# 2_0.net
KiCad netlist of a schematic drawn in Altium Designer
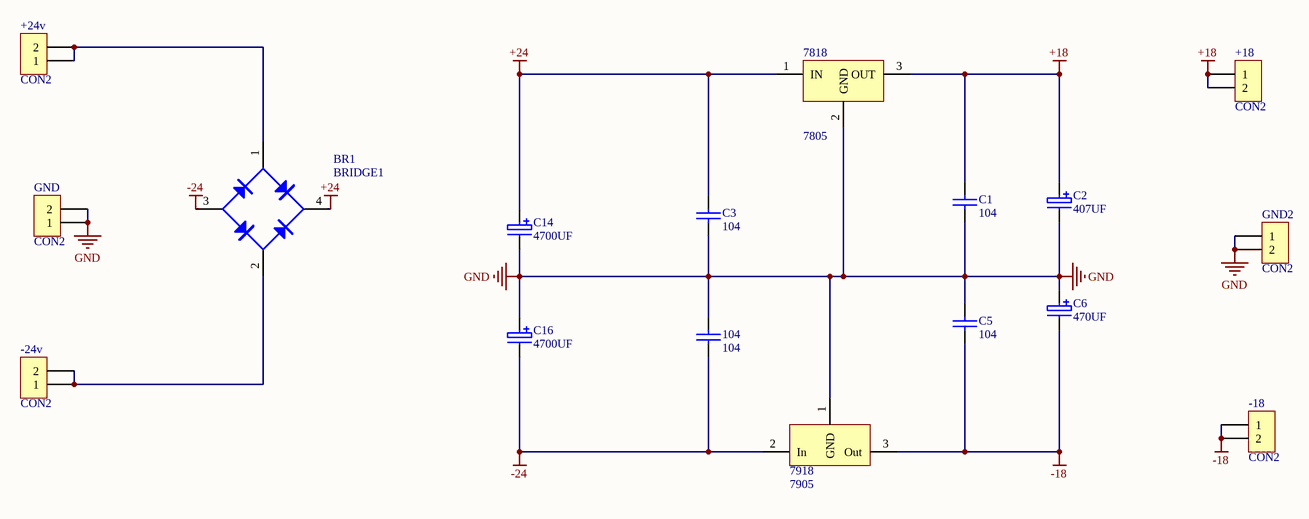
[diagram p0: 电源2.0.SchDoc]

(export (version "E")
  (design (tool "Eeschema 10.0.6"))
  (components
    (comp (ref "+18")
      (value "CON2")
      (footprint "2P-200")
      (description "Connector")
      (libsource (lib "接口") (part "CON2"))
    )
    (comp (ref "+24v")
      (value "CON2")
      (footprint "2P-200")
      (description "Connector")
      (libsource (lib "") (part "CON2_1"))
    )
    (comp (ref "-18")
      (value "CON2")
      (footprint "2P-200")
      (description "Connector")
      (libsource (lib "接口") (part "CON2"))
    )
    (comp (ref "-24v")
      (value "CON2")
      (footprint "2P-200")
      (description "Connector")
      (libsource (lib "") (part "CON2_1"))
    )
    (comp (ref "104") (value "104") (footprint "CAP2") (libsource (lib "C电容") (part "CAP1")))
    (comp (ref "7818") (value "7805") (footprint "TO-220") (libsource (lib "稳压管") (part "7805")))
    (comp (ref "7918") (value "7905") (footprint "TO-220") (libsource (lib "稳压管") (part "7905")))
    (comp (ref "BR1")
      (value "BRIDGE1")
      (footprint "D3")
      (description "BR")
      (libsource (lib "D硅堆") (part "BRIDGE1"))
    )
    (comp (ref "C1") (value "104") (footprint "CAP2") (libsource (lib "C电容") (part "CAP1")))
    (comp (ref "C2") (value "407UF") (footprint "CAO5") (libsource (lib "C电容") (part "CAP3")))
    (comp (ref "C3") (value "104") (footprint "CAP2") (libsource (lib "C电容") (part "CAP1")))
    (comp (ref "C5") (value "104") (footprint "CAP2") (libsource (lib "C电容") (part "CAP1")))
    (comp (ref "C6") (value "470UF") (footprint "CAO5") (libsource (lib "C电容") (part "CAP3")))
    (comp (ref "C14") (value "4700UF") (footprint "C22") (libsource (lib "C电容") (part "CAP3")))
    (comp (ref "C16") (value "4700UF") (footprint "C22") (libsource (lib "C电容") (part "CAP3")))
    (comp (ref "GND")
      (value "CON2")
      (footprint "2P-200")
      (description "Connector")
      (libsource (lib "") (part "CON2_1"))
    )
    (comp (ref "GND2")
      (value "CON2")
      (footprint "2P-200")
      (description "Connector")
      (libsource (lib "接口") (part "CON2"))
    )
  )
  (nets
    (net (code "1") (name "+18") (class "Default")
      (node (ref "+18") (pin "1") (pinfunction "1_1") (pintype "passive"))
      (node (ref "+18") (pin "2") (pinfunction "2_2") (pintype "passive"))
      (node (ref "7818") (pin "3") (pinfunction "OUT_3") (pintype "passive"))
      (node (ref "C1") (pin "1") (pinfunction "1_1") (pintype "passive"))
      (node (ref "C2") (pin "1") (pintype "passive"))
    )
    (net (code "2") (name "+24") (class "Default")
      (node (ref "7818") (pin "1") (pinfunction "IN_1") (pintype "passive"))
      (node (ref "BR1") (pin "4") (pinfunction "V+_4") (pintype "passive"))
      (node (ref "C14") (pin "1") (pintype "passive"))
      (node (ref "C3") (pin "1") (pinfunction "1_1") (pintype "passive"))
    )
    (net (code "3") (name "-18") (class "Default")
      (node (ref "-18") (pin "1") (pinfunction "1_1") (pintype "passive"))
      (node (ref "-18") (pin "2") (pinfunction "2_2") (pintype "passive"))
      (node (ref "7918") (pin "3") (pinfunction "Out_3") (pintype "passive"))
      (node (ref "C5") (pin "2") (pinfunction "2_2") (pintype "passive"))
      (node (ref "C6") (pin "2") (pintype "passive"))
    )
    (net (code "4") (name "-24") (class "Default")
      (node (ref "104") (pin "2") (pinfunction "2_2") (pintype "passive"))
      (node (ref "7918") (pin "2") (pinfunction "In_2") (pintype "passive"))
      (node (ref "BR1") (pin "3") (pinfunction "V-_3") (pintype "passive"))
      (node (ref "C16") (pin "2") (pintype "passive"))
    )
    (net (code "5") (name "GND") (class "Default")
      (node (ref "104") (pin "1") (pinfunction "1_1") (pintype "passive"))
      (node (ref "7818") (pin "2") (pinfunction "GND_2") (pintype "passive"))
      (node (ref "7918") (pin "1") (pinfunction "GND_1") (pintype "passive"))
      (node (ref "C1") (pin "2") (pinfunction "2_2") (pintype "passive"))
      (node (ref "C14") (pin "2") (pintype "passive"))
      (node (ref "C16") (pin "1") (pintype "passive"))
      (node (ref "C2") (pin "2") (pintype "passive"))
      (node (ref "C3") (pin "2") (pinfunction "2_2") (pintype "passive"))
      (node (ref "C5") (pin "1") (pinfunction "1_1") (pintype "passive"))
      (node (ref "C6") (pin "1") (pintype "passive"))
      (node (ref "GND") (pin "1") (pinfunction "1_1") (pintype "passive"))
      (node (ref "GND") (pin "2") (pinfunction "2_2") (pintype "passive"))
      (node (ref "GND2") (pin "1") (pinfunction "1_1") (pintype "passive"))
      (node (ref "GND2") (pin "2") (pinfunction "2_2") (pintype "passive"))
    )
    (net (code "6") (name "Net-(BR1-AC1)") (class "Default")
      (node (ref "+24v") (pin "1") (pinfunction "1_1") (pintype "passive"))
      (node (ref "+24v") (pin "2") (pinfunction "2_2") (pintype "passive"))
      (node (ref "BR1") (pin "1") (pinfunction "AC1_1") (pintype "passive"))
    )
    (net (code "7") (name "Net-(BR1-AC2)") (class "Default")
      (node (ref "-24v") (pin "1") (pinfunction "1_1") (pintype "passive"))
      (node (ref "-24v") (pin "2") (pinfunction "2_2") (pintype "passive"))
      (node (ref "BR1") (pin "2") (pinfunction "AC2_2") (pintype "passive"))
    )
  )
)
